# ADSR_duino.net
KiCad netlist of a schematic drawn in EAGLE
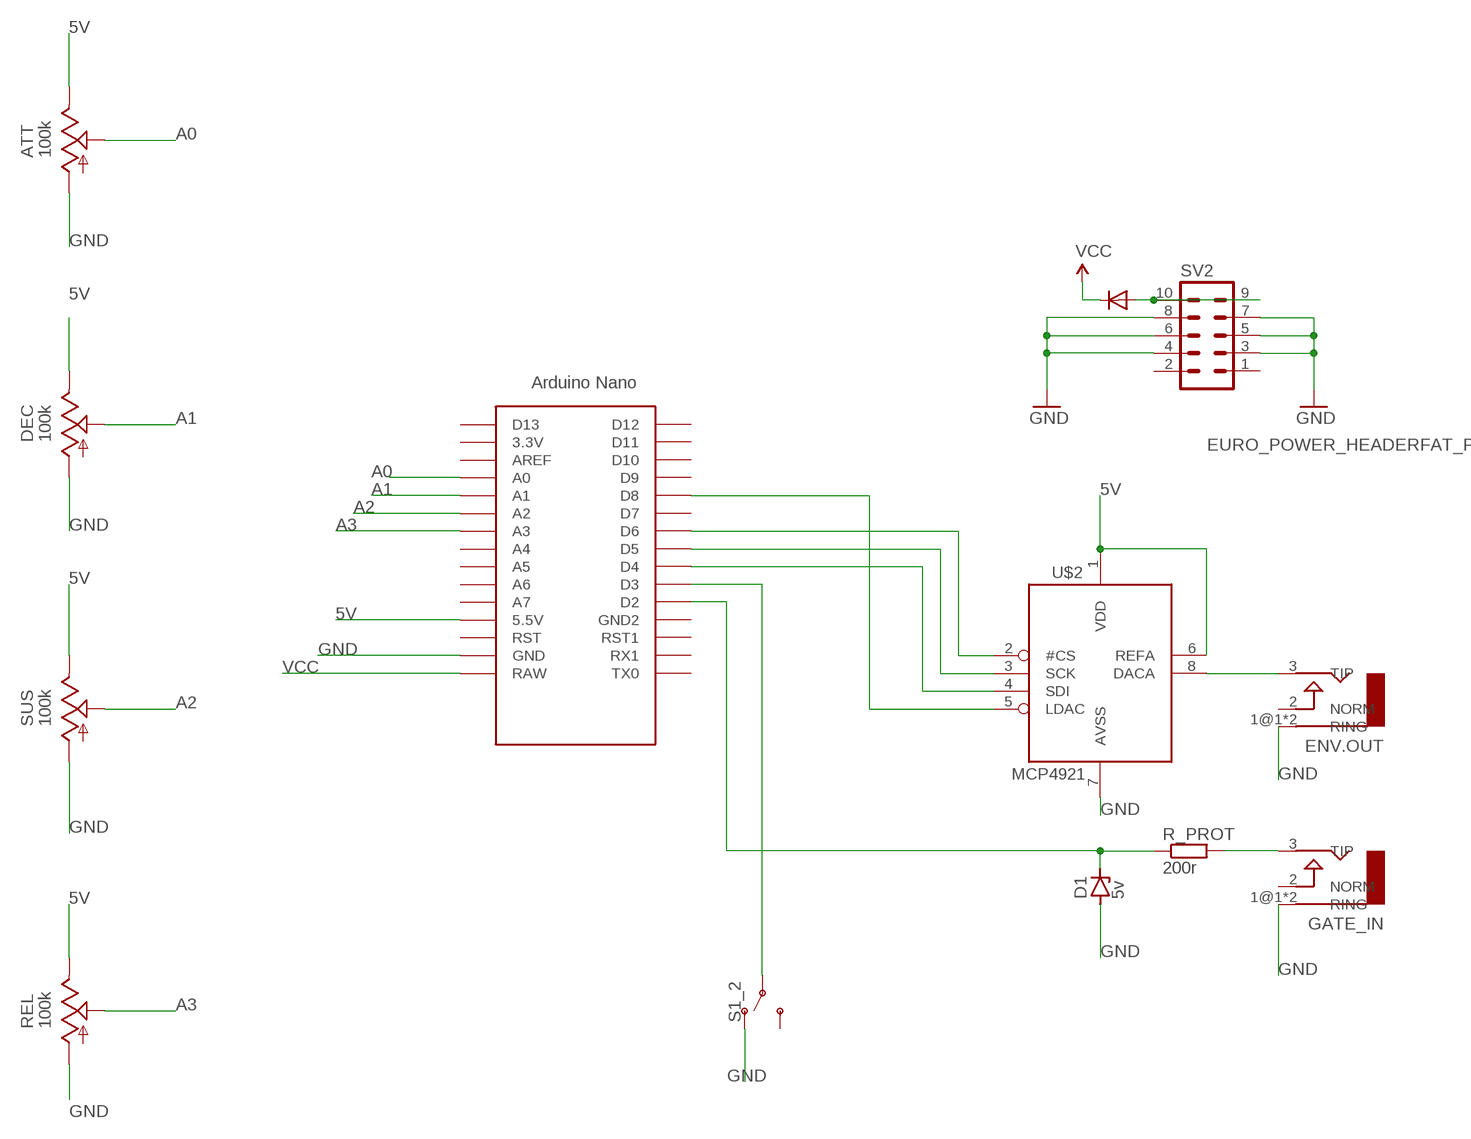
[diagram p0: schematic, sheet 1]

(export (version "E")
  (design (tool "Eeschema 10.0.6"))
  (components
    (comp (ref "ATT")
      (value "100k")
      (footprint "eagle-import:SLIDEPOT-45")
      (libsource (lib "eagle-import") (part "TRIMSLIDE45"))
    )
    (comp (ref "D1")
      (value "5v")
      (footprint "eagle-import:ZDIO-5")
      (libsource (lib "eagle-import") (part "ZENER-DIODEZD-5"))
    )
    (comp (ref "D2")
      (value "1N5819HW")
      (footprint "eagle-import:DO-1N4148")
      (libsource (lib "eagle-import") (part "DIODEDO-1N4148"))
    )
    (comp (ref "DEC")
      (value "100k")
      (footprint "eagle-import:SLIDEPOT-45")
      (libsource (lib "eagle-import") (part "TRIMSLIDE45"))
    )
    (comp (ref "ENV.OUT")
      (value "AUDIO-JACKERTHENVAR")
      (footprint "eagle-import:ERTHENVAR-JACK")
      (libsource (lib "eagle-import") (part "AUDIO-JACKERTHENVAR"))
    )
    (comp (ref "GATE_IN")
      (value "AUDIO-JACKERTHENVAR")
      (footprint "eagle-import:ERTHENVAR-JACK")
      (libsource (lib "eagle-import") (part "AUDIO-JACKERTHENVAR"))
    )
    (comp (ref "REL")
      (value "100k")
      (footprint "eagle-import:SLIDEPOT-45")
      (libsource (lib "eagle-import") (part "TRIMSLIDE45"))
    )
    (comp (ref "R_PROT")
      (value "200r")
      (footprint "eagle-import:7MM_RESISTOR")
      (libsource (lib "eagle-import") (part "RESISTOR7MM"))
    )
    (comp (ref "S1_2")
      (value "SWITCH-SPDT-PTH-11.6X4.0MM")
      (footprint "eagle-import:SWITCH_SPDT_PTH_11.6X4.0MM")
      (libsource (lib "eagle-import") (part "SWITCH-SPDT-PTH-11.6X4.0MM"))
    )
    (comp (ref "SUS")
      (value "100k")
      (footprint "eagle-import:SLIDEPOT-45")
      (libsource (lib "eagle-import") (part "TRIMSLIDE45"))
    )
    (comp (ref "SV2")
      (value "EURO_POWER_HEADERFAT_PADS")
      (footprint "eagle-import:EURO_PWR_HEADER_FAT")
      (libsource (lib "eagle-import") (part "EURO_POWER_HEADERFAT_PADS"))
    )
    (comp (ref "U$1")
      (value "NANO")
      (footprint "eagle-import:NANO")
      (libsource (lib "eagle-import") (part "NANO"))
    )
    (comp (ref "U$2")
      (value "MCP4921")
      (footprint "eagle-import:DIL08")
      (libsource (lib "eagle-import") (part "MCP4921"))
    )
  )
  (nets
    (net (code "1") (name "/5V") (class "Default")
      (node (ref "ATT") (pin "B") (pinfunction "B_B") (pintype "passive"))
      (node (ref "DEC") (pin "B") (pinfunction "B_B") (pintype "passive"))
      (node (ref "REL") (pin "B") (pinfunction "B_B") (pintype "passive"))
      (node (ref "SUS") (pin "B") (pinfunction "B_B") (pintype "passive"))
      (node (ref "U$1") (pin "5V") (pinfunction "5.5V_5V") (pintype "bidirectional"))
      (node (ref "U$2") (pin "1") (pinfunction "VDD_1") (pintype "power_in"))
      (node (ref "U$2") (pin "6") (pinfunction "REFA_6") (pintype "input"))
    )
    (net (code "2") (name "/A0") (class "Default")
      (node (ref "ATT") (pin "WIPER") (pinfunction "WIPER_WIPER") (pintype "passive"))
      (node (ref "U$1") (pin "A0") (pinfunction "A0_A0") (pintype "bidirectional"))
    )
    (net (code "3") (name "/A1") (class "Default")
      (node (ref "DEC") (pin "WIPER") (pinfunction "WIPER_WIPER") (pintype "passive"))
      (node (ref "U$1") (pin "A1") (pinfunction "A1_A1") (pintype "bidirectional"))
    )
    (net (code "4") (name "/A2") (class "Default")
      (node (ref "SUS") (pin "WIPER") (pinfunction "WIPER_WIPER") (pintype "passive"))
      (node (ref "U$1") (pin "A2") (pinfunction "A2_A2") (pintype "bidirectional"))
    )
    (net (code "5") (name "/A3") (class "Default")
      (node (ref "REL") (pin "WIPER") (pinfunction "WIPER_WIPER") (pintype "passive"))
      (node (ref "U$1") (pin "A3") (pinfunction "A3_A3") (pintype "bidirectional"))
    )
    (net (code "6") (name "GND") (class "Default")
      (node (ref "ATT") (pin "A") (pinfunction "A_A") (pintype "passive"))
      (node (ref "D1") (pin "A") (pinfunction "A_A") (pintype "passive"))
      (node (ref "DEC") (pin "A") (pinfunction "A_A") (pintype "passive"))
      (node (ref "ENV.OUT") (pin "1@1") (pinfunction "RING_1@1") (pintype "bidirectional"))
      (node (ref "ENV.OUT") (pin "1@2") (pinfunction "RING_1@2") (pintype "bidirectional"))
      (node (ref "GATE_IN") (pin "1@1") (pinfunction "RING_1@1") (pintype "bidirectional"))
      (node (ref "GATE_IN") (pin "1@2") (pinfunction "RING_1@2") (pintype "bidirectional"))
      (node (ref "REL") (pin "A") (pinfunction "A_A") (pintype "passive"))
      (node (ref "S1_2") (pin "1") (pinfunction "O_1") (pintype "passive"))
      (node (ref "SUS") (pin "A") (pinfunction "A_A") (pintype "passive"))
      (node (ref "SV2") (pin "3") (pinfunction "3_3") (pintype "passive"))
      (node (ref "SV2") (pin "4") (pinfunction "4_4") (pintype "passive"))
      (node (ref "SV2") (pin "5") (pinfunction "5_5") (pintype "passive"))
      (node (ref "SV2") (pin "6") (pinfunction "6_6") (pintype "passive"))
      (node (ref "SV2") (pin "7") (pinfunction "7_7") (pintype "passive"))
      (node (ref "SV2") (pin "8") (pinfunction "8_8") (pintype "passive"))
      (node (ref "U$1") (pin "GND") (pinfunction "GND_GND") (pintype "bidirectional"))
      (node (ref "U$2") (pin "7") (pinfunction "AVSS_7") (pintype "power_in"))
    )
    (net (code "7") (name "Net-(D1-PadC)") (class "Default")
      (node (ref "D1") (pin "C") (pinfunction "C_C") (pintype "passive"))
      (node (ref "R_PROT") (pin "1") (pinfunction "1_1") (pintype "passive"))
      (node (ref "U$1") (pin "D2") (pinfunction "D2_D2") (pintype "bidirectional"))
    )
    (net (code "8") (name "Net-(D2-PadA)") (class "Default")
      (node (ref "D2") (pin "A") (pinfunction "A_A") (pintype "passive"))
      (node (ref "SV2") (pin "10") (pinfunction "10_10") (pintype "passive"))
      (node (ref "SV2") (pin "9") (pinfunction "9_9") (pintype "passive"))
    )
    (net (code "9") (name "Net-(ENV.OUT-TIP)") (class "Default")
      (node (ref "ENV.OUT") (pin "3") (pinfunction "TIP_3") (pintype "bidirectional"))
      (node (ref "U$2") (pin "8") (pinfunction "DACA_8") (pintype "output"))
    )
    (net (code "10") (name "Net-(GATE_IN-TIP)") (class "Default")
      (node (ref "GATE_IN") (pin "3") (pinfunction "TIP_3") (pintype "bidirectional"))
      (node (ref "R_PROT") (pin "2") (pinfunction "2_2") (pintype "passive"))
    )
    (net (code "11") (name "Net-(S1_2-P)") (class "Default")
      (node (ref "S1_2") (pin "2") (pinfunction "P_2") (pintype "passive"))
      (node (ref "U$1") (pin "D3") (pinfunction "D3_D3") (pintype "bidirectional"))
    )
    (net (code "12") (name "Net-(U$2-#CS)") (class "Default")
      (node (ref "U$1") (pin "D6") (pinfunction "D6_D6") (pintype "bidirectional"))
      (node (ref "U$2") (pin "2") (pinfunction "#CS_2") (pintype "input"))
    )
    (net (code "13") (name "Net-(U$2-LDAC)") (class "Default")
      (node (ref "U$1") (pin "D8") (pinfunction "D8_D8") (pintype "bidirectional"))
      (node (ref "U$2") (pin "5") (pinfunction "LDAC_5") (pintype "input"))
    )
    (net (code "14") (name "Net-(U$2-SCK)") (class "Default")
      (node (ref "U$1") (pin "D5") (pinfunction "D5_D5") (pintype "bidirectional"))
      (node (ref "U$2") (pin "3") (pinfunction "SCK_3") (pintype "input"))
    )
    (net (code "15") (name "Net-(U$2-SDI)") (class "Default")
      (node (ref "U$1") (pin "D4") (pinfunction "D4_D4") (pintype "bidirectional"))
      (node (ref "U$2") (pin "4") (pinfunction "SDI_4") (pintype "input"))
    )
    (net (code "16") (name "VCC") (class "Default")
      (node (ref "D2") (pin "C") (pinfunction "C_C") (pintype "passive"))
      (node (ref "U$1") (pin "RAW") (pinfunction "RAW_RAW") (pintype "bidirectional"))
    )
    (net (code "17") (name "unconnected-(ENV.OUT-NORM-Pad2)") (class "Default")
      (node (ref "ENV.OUT") (pin "2") (pinfunction "NORM_2") (pintype "bidirectional"))
    )
    (net (code "18") (name "unconnected-(GATE_IN-NORM-Pad2)") (class "Default")
      (node (ref "GATE_IN") (pin "2") (pinfunction "NORM_2") (pintype "bidirectional"))
    )
    (net (code "19") (name "unconnected-(S1_2-S-Pad3)") (class "Default")
      (node (ref "S1_2") (pin "3") (pinfunction "S_3") (pintype "passive"))
    )
    (net (code "20") (name "unconnected-(SV2-Pad1)") (class "Default")
      (node (ref "SV2") (pin "1") (pinfunction "1_1") (pintype "passive"))
    )
    (net (code "21") (name "unconnected-(SV2-Pad2)") (class "Default")
      (node (ref "SV2") (pin "2") (pinfunction "2_2") (pintype "passive"))
    )
    (net (code "22") (name "unconnected-(U$1-GND2-PadGND1)") (class "Default")
      (node (ref "U$1") (pin "GND1") (pinfunction "GND2_GND1") (pintype "bidirectional"))
    )
    (net (code "23") (name "unconnected-(U$1-Pad3.3V)") (class "Default")
      (node (ref "U$1") (pin "3.3V") (pinfunction "3.3V_3.3V") (pintype "bidirectional"))
    )
    (net (code "24") (name "unconnected-(U$1-PadA4)") (class "Default")
      (node (ref "U$1") (pin "A4") (pinfunction "A4_A4") (pintype "bidirectional"))
    )
    (net (code "25") (name "unconnected-(U$1-PadA5)") (class "Default")
      (node (ref "U$1") (pin "A5") (pinfunction "A5_A5") (pintype "bidirectional"))
    )
    (net (code "26") (name "unconnected-(U$1-PadA6)") (class "Default")
      (node (ref "U$1") (pin "A6") (pinfunction "A6_A6") (pintype "bidirectional"))
    )
    (net (code "27") (name "unconnected-(U$1-PadA7)") (class "Default")
      (node (ref "U$1") (pin "A7") (pinfunction "A7_A7") (pintype "bidirectional"))
    )
    (net (code "28") (name "unconnected-(U$1-PadAREF)") (class "Default")
      (node (ref "U$1") (pin "AREF") (pinfunction "AREF_AREF") (pintype "bidirectional"))
    )
    (net (code "29") (name "unconnected-(U$1-PadD7)") (class "Default")
      (node (ref "U$1") (pin "D7") (pinfunction "D7_D7") (pintype "bidirectional"))
    )
    (net (code "30") (name "unconnected-(U$1-PadD9)") (class "Default")
      (node (ref "U$1") (pin "D9") (pinfunction "D9_D9") (pintype "bidirectional"))
    )
    (net (code "31") (name "unconnected-(U$1-PadD10)") (class "Default")
      (node (ref "U$1") (pin "D10") (pinfunction "D10_D10") (pintype "bidirectional"))
    )
    (net (code "32") (name "unconnected-(U$1-PadD11)") (class "Default")
      (node (ref "U$1") (pin "D11") (pinfunction "D11_D11") (pintype "bidirectional"))
    )
    (net (code "33") (name "unconnected-(U$1-PadD12)") (class "Default")
      (node (ref "U$1") (pin "D12") (pinfunction "D12_D12") (pintype "bidirectional"))
    )
    (net (code "34") (name "unconnected-(U$1-PadD13)") (class "Default")
      (node (ref "U$1") (pin "D13") (pinfunction "D13_D13") (pintype "bidirectional"))
    )
    (net (code "35") (name "unconnected-(U$1-PadRST)") (class "Default")
      (node (ref "U$1") (pin "RST") (pinfunction "RST_RST") (pintype "bidirectional"))
    )
    (net (code "36") (name "unconnected-(U$1-PadRST1)") (class "Default")
      (node (ref "U$1") (pin "RST1") (pinfunction "RST1_RST1") (pintype "bidirectional"))
    )
    (net (code "37") (name "unconnected-(U$1-PadRX1)") (class "Default")
      (node (ref "U$1") (pin "RX1") (pinfunction "RX1_RX1") (pintype "bidirectional"))
    )
    (net (code "38") (name "unconnected-(U$1-PadTX0)") (class "Default")
      (node (ref "U$1") (pin "TX0") (pinfunction "TX0_TX0") (pintype "bidirectional"))
    )
  )
)
